# LoRaCam.net
KiCad netlist of a schematic drawn in EasyEDA
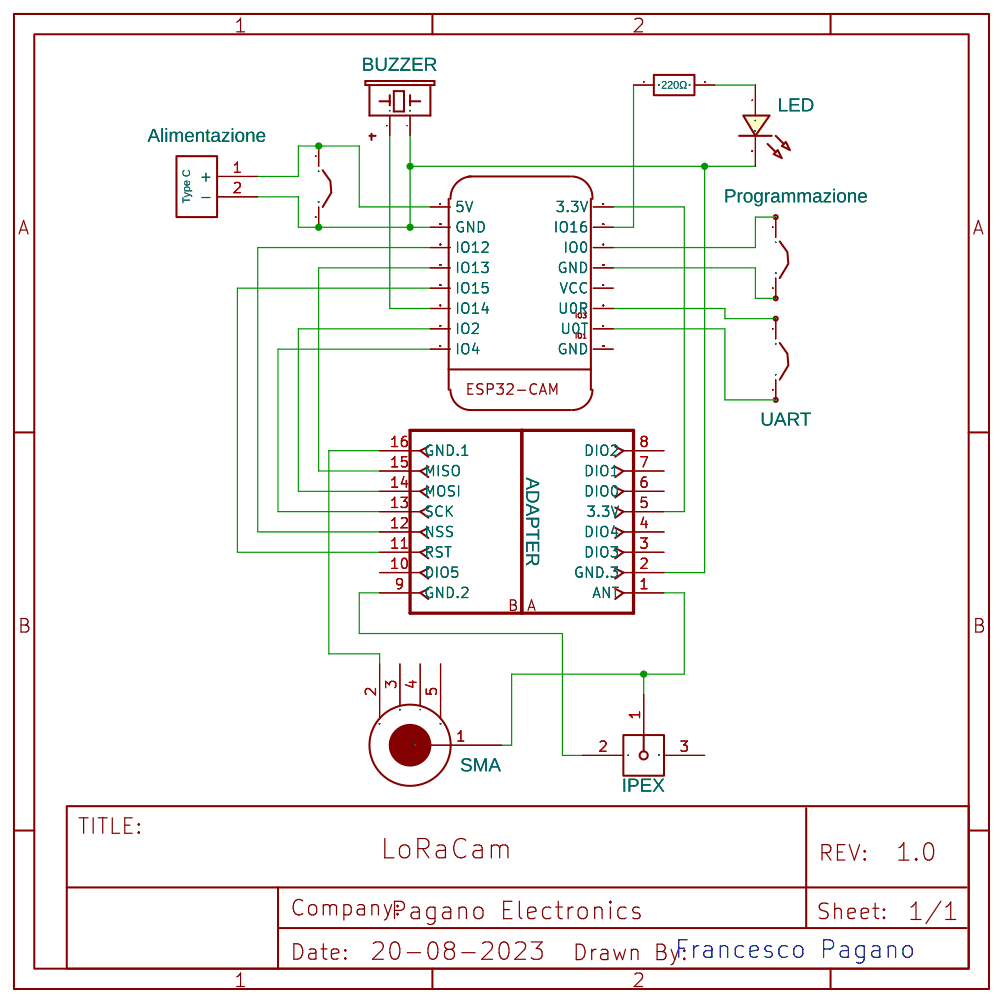
[diagram p0: schematic sheet]

(export (version "E")
  (design (tool "Eeschema 10.0.6"))
  (components
    (comp (ref "B") (value "BUZZER") (libsource (lib "") (part "BUZZER")))
    (comp (ref "ESP32CAM") (value "ESP32CAM") (libsource (lib "") (part "ESP32CAM")))
    (comp (ref "IPEX")
      (value "IPEX")
      (fields
        (field (name "Manufacturer Part") "HC-RF-IPEX0303-01")
        (field (name "Manufacturer") "HCTL(华灿天禄)")
      )
      (libsource (lib "") (part "IPEX"))
    )
    (comp (ref "J1")
      (value "Programmazione")
      (fields (field (name "Manufacturer Part") "NONE"))
      (libsource (lib "") (part "JUMPERTHRUHOLE"))
    )
    (comp (ref "J2")
      (value "UART")
      (fields (field (name "Manufacturer Part") "NONE"))
      (libsource (lib "") (part "JUMPERTHRUHOLE"))
    )
    (comp (ref "J3")
      (value "Alimentazione")
      (fields (field (name "Manufacturer Part") "NONE"))
      (libsource (lib "") (part "JUMPERTHRUHOLE"))
    )
    (comp (ref "LED")
      (value "LED")
      (fields
        (field (name "Manufacturer Part") "204-10SDRD/S530-A3-L")
        (field (name "Manufacturer") "EVERLIGHT(台湾亿光)")
      )
      (libsource (lib "") (part "LED-TH-3mm_R"))
    )
    (comp (ref "LORA") (value "ADAPTER") (libsource (lib "") (part "ESP8266-WITH-ADAPTER")))
    (comp (ref "R1") (value "220Ω") (libsource (lib "") (part "R_0603_EU")))
    (comp (ref "SMA")
      (value "SMA")
      (fields (field (name "Manufacturer Part") "SMA-VERTICAL") (field (name "Manufacturer") "SHIVRAM"))
      (libsource (lib "") (part "SMA FEMALE VERTICAL MOUNT"))
    )
    (comp (ref "TYPEC") (value "Type C") (libsource (lib "") (part "usb type C 2 pin")))
  )
  (nets
    (net (code "1") (name "Net-(B-1)") (class "Default")
      (node (ref "B") (pin "+") (pinfunction "1_+") (pintype "unspecified"))
      (node (ref "ESP32CAM") (pin "IO14") (pinfunction "IO14_IO14") (pintype "bidirectional"))
    )
    (net (code "2") (name "Net-(B-2)") (class "Default")
      (node (ref "B") (pin "-") (pinfunction "2_-") (pintype "unspecified"))
      (node (ref "ESP32CAM") (pin "GND@1") (pinfunction "GND_GND@1") (pintype "bidirectional"))
      (node (ref "J3") (pin "2") (pinfunction "2_2") (pintype "unspecified"))
      (node (ref "LED") (pin "2") (pinfunction "2_2") (pintype "unspecified"))
      (node (ref "LORA") (pin "2") (pinfunction "GND.3_2") (pintype "bidirectional"))
      (node (ref "TYPEC") (pin "2") (pinfunction "-_2") (pintype "unspecified"))
    )
    (net (code "3") (name "Net-(ESP32CAM-GND-PadGND@2)") (class "Default")
      (node (ref "ESP32CAM") (pin "GND@2") (pinfunction "GND_GND@2") (pintype "bidirectional"))
      (node (ref "J1") (pin "2") (pinfunction "2_2") (pintype "unspecified"))
    )
    (net (code "4") (name "Net-(ESP32CAM-PadIO0)") (class "Default")
      (node (ref "ESP32CAM") (pin "IO0") (pinfunction "IO0_IO0") (pintype "bidirectional"))
      (node (ref "J1") (pin "1") (pinfunction "1_1") (pintype "unspecified"))
    )
    (net (code "5") (name "Net-(ESP32CAM-PadIO16)") (class "Default")
      (node (ref "ESP32CAM") (pin "IO16") (pinfunction "IO16_IO16") (pintype "bidirectional"))
      (node (ref "R1") (pin "1") (pinfunction "1_1") (pintype "unspecified"))
    )
    (net (code "6") (name "Net-(ESP32CAM-U0R)") (class "Default")
      (node (ref "ESP32CAM") (pin "UDR") (pinfunction "U0R_UDR") (pintype "bidirectional"))
      (node (ref "J2") (pin "1") (pinfunction "1_1") (pintype "unspecified"))
    )
    (net (code "7") (name "Net-(ESP32CAM-U0T)") (class "Default")
      (node (ref "ESP32CAM") (pin "UDT") (pinfunction "U0T_UDT") (pintype "bidirectional"))
      (node (ref "J2") (pin "2") (pinfunction "2_2") (pintype "unspecified"))
    )
    (net (code "8") (name "Net-(LED-Pad1)") (class "Default")
      (node (ref "LED") (pin "1") (pinfunction "1_1") (pintype "unspecified"))
      (node (ref "R1") (pin "2") (pinfunction "2_2") (pintype "unspecified"))
    )
    (net (code "9") (name "Net-(LORA-3.3V)") (class "Default")
      (node (ref "ESP32CAM") (pin "3.3V") (pinfunction "3.3V_3.3V") (pintype "bidirectional"))
      (node (ref "LORA") (pin "5") (pinfunction "3.3V_5") (pintype "bidirectional"))
    )
    (net (code "10") (name "Net-(LORA-ANT)") (class "Default")
      (node (ref "IPEX") (pin "1") (pinfunction "1_1") (pintype "unspecified"))
      (node (ref "LORA") (pin "1") (pinfunction "ANT_1") (pintype "bidirectional"))
      (node (ref "SMA") (pin "1") (pinfunction "1_1") (pintype "unspecified"))
    )
    (net (code "11") (name "Net-(LORA-GND.1)") (class "Default")
      (node (ref "LORA") (pin "16") (pinfunction "GND.1_16") (pintype "bidirectional"))
      (node (ref "SMA") (pin "2") (pinfunction "2_2") (pintype "unspecified"))
    )
    (net (code "12") (name "Net-(LORA-GND.2)") (class "Default")
      (node (ref "IPEX") (pin "2") (pinfunction "2_2") (pintype "unspecified"))
      (node (ref "LORA") (pin "9") (pinfunction "GND.2_9") (pintype "bidirectional"))
    )
    (net (code "13") (name "Net-(LORA-MISO)") (class "Default")
      (node (ref "ESP32CAM") (pin "IO13") (pinfunction "IO13_IO13") (pintype "bidirectional"))
      (node (ref "LORA") (pin "15") (pinfunction "MISO_15") (pintype "bidirectional"))
    )
    (net (code "14") (name "Net-(LORA-MOSI)") (class "Default")
      (node (ref "ESP32CAM") (pin "IO2") (pinfunction "IO2_IO2") (pintype "bidirectional"))
      (node (ref "LORA") (pin "14") (pinfunction "MOSI_14") (pintype "bidirectional"))
    )
    (net (code "15") (name "Net-(LORA-NSS)") (class "Default")
      (node (ref "ESP32CAM") (pin "IO12") (pinfunction "IO12_IO12") (pintype "bidirectional"))
      (node (ref "LORA") (pin "12") (pinfunction "NSS_12") (pintype "bidirectional"))
    )
    (net (code "16") (name "Net-(LORA-RST)") (class "Default")
      (node (ref "ESP32CAM") (pin "IO15") (pinfunction "IO15_IO15") (pintype "bidirectional"))
      (node (ref "LORA") (pin "11") (pinfunction "RST_11") (pintype "bidirectional"))
    )
    (net (code "17") (name "Net-(LORA-SCK)") (class "Default")
      (node (ref "ESP32CAM") (pin "IO4") (pinfunction "IO4_IO4") (pintype "bidirectional"))
      (node (ref "LORA") (pin "13") (pinfunction "SCK_13") (pintype "bidirectional"))
    )
    (net (code "18") (name "Net-(TYPEC-+)") (class "Default")
      (node (ref "ESP32CAM") (pin "5V") (pinfunction "5V_5V") (pintype "bidirectional"))
      (node (ref "J3") (pin "1") (pinfunction "1_1") (pintype "unspecified"))
      (node (ref "TYPEC") (pin "1") (pinfunction "+_1") (pintype "unspecified"))
    )
    (net (code "19") (name "unconnected-(ESP32CAM-GND-PadGND@3)") (class "Default")
      (node (ref "ESP32CAM") (pin "GND@3") (pinfunction "GND_GND@3") (pintype "bidirectional"))
    )
    (net (code "20") (name "unconnected-(ESP32CAM-PadVCC)") (class "Default")
      (node (ref "ESP32CAM") (pin "VCC") (pinfunction "VCC_VCC") (pintype "bidirectional"))
    )
    (net (code "21") (name "unconnected-(IPEX-Pad3)") (class "Default")
      (node (ref "IPEX") (pin "3") (pinfunction "3_3") (pintype "unspecified"))
    )
    (net (code "22") (name "unconnected-(LORA-DIO0-Pad6)") (class "Default")
      (node (ref "LORA") (pin "6") (pinfunction "DIO0_6") (pintype "bidirectional"))
    )
    (net (code "23") (name "unconnected-(LORA-DIO1-Pad7)") (class "Default")
      (node (ref "LORA") (pin "7") (pinfunction "DIO1_7") (pintype "bidirectional"))
    )
    (net (code "24") (name "unconnected-(LORA-DIO2-Pad8)") (class "Default")
      (node (ref "LORA") (pin "8") (pinfunction "DIO2_8") (pintype "bidirectional"))
    )
    (net (code "25") (name "unconnected-(LORA-DIO3-Pad3)") (class "Default")
      (node (ref "LORA") (pin "3") (pinfunction "DIO3_3") (pintype "bidirectional"))
    )
    (net (code "26") (name "unconnected-(LORA-DIO4-Pad4)") (class "Default")
      (node (ref "LORA") (pin "4") (pinfunction "DIO4_4") (pintype "bidirectional"))
    )
    (net (code "27") (name "unconnected-(LORA-DIO5-Pad10)") (class "Default")
      (node (ref "LORA") (pin "10") (pinfunction "DIO5_10") (pintype "bidirectional"))
    )
    (net (code "28") (name "unconnected-(SMA-Pad3)") (class "Default")
      (node (ref "SMA") (pin "3") (pinfunction "3_3") (pintype "unspecified"))
    )
    (net (code "29") (name "unconnected-(SMA-Pad4)") (class "Default")
      (node (ref "SMA") (pin "4") (pinfunction "4_4") (pintype "unspecified"))
    )
    (net (code "30") (name "unconnected-(SMA-Pad5)") (class "Default")
      (node (ref "SMA") (pin "5") (pinfunction "5_5") (pintype "unspecified"))
    )
  )
)
